# USBHeaders.net
KiCad netlist of a schematic drawn in Altium Designer
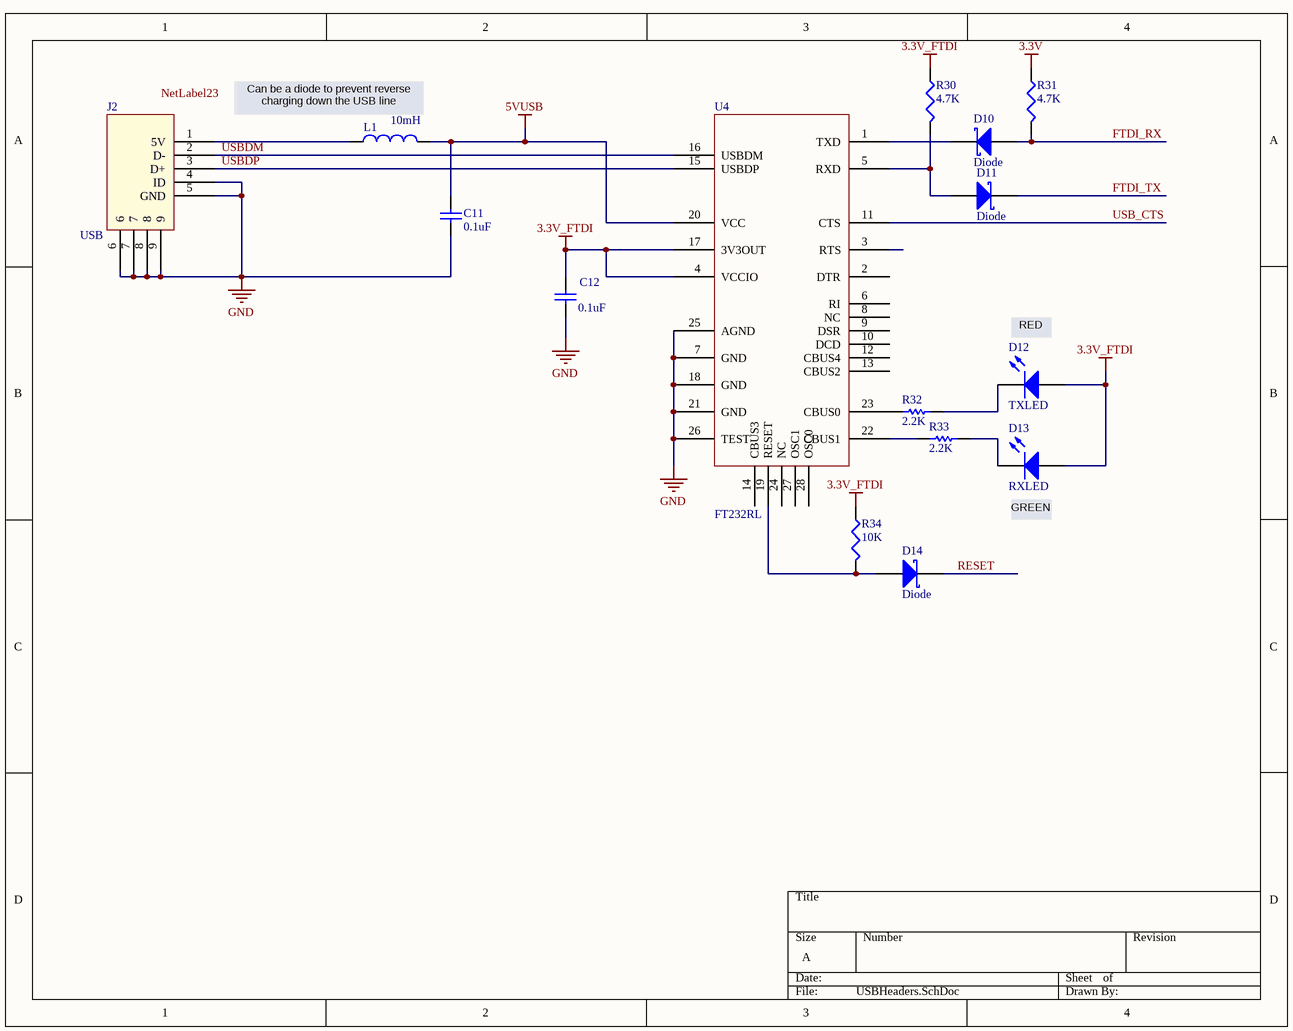
[diagram p0: USBHeaders.SchDoc]

(export (version "E")
  (design (tool "Eeschema 10.0.6"))
  (components
    (comp (ref "C11")
      (value "0.1uF")
      (footprint "0402")
      (description "Capacitor")
      (fields (field (name "PUBLISHER") "Altium Limited"))
      (libsource (lib "Miscellaneous Devices") (part "Cap"))
    )
    (comp (ref "C12")
      (value "0.1uF")
      (footprint "0402")
      (description "Capacitor")
      (fields (field (name "PUBLISHER") "Altium Limited"))
      (libsource (lib "Miscellaneous Devices") (part "Cap"))
    )
    (comp (ref "D10")
      (value "Diode")
      (footprint "SurfaceMount(603)")
      (libsource (lib "mrone") (part "SchottkeyDiode"))
    )
    (comp (ref "D11")
      (value "Diode")
      (footprint "SurfaceMount(603)")
      (libsource (lib "mrone") (part "SchottkeyDiode"))
    )
    (comp (ref "D12")
      (value "TXLED")
      (footprint "SurfaceMount(603)")
      (description "Typical RED, GREEN, YELLOW, AMBER GaAs LED")
      (fields (field (name "PUBLISHER") "Altium Limited"))
      (libsource (lib "Miscellaneous Devices") (part "LED2"))
    )
    (comp (ref "D13")
      (value "RXLED")
      (footprint "SurfaceMount(603)")
      (description "Typical RED, GREEN, YELLOW, AMBER GaAs LED")
      (fields (field (name "PUBLISHER") "Altium Limited"))
      (libsource (lib "Miscellaneous Devices") (part "LED2"))
    )
    (comp (ref "D14")
      (value "Diode")
      (footprint "SurfaceMount(603)")
      (libsource (lib "mrone") (part "SchottkeyDiode"))
    )
    (comp (ref "J2")
      (value "USB")
      (footprint "USB Minib (thru-hole)")
      (libsource (lib "mrone") (part "USB-ConnTH"))
    )
    (comp (ref "L1")
      (value "10mH")
      (footprint "2029")
      (description "Inductor")
      (fields (field (name "PUBLISHER") "Altium Limited"))
      (libsource (lib "Miscellaneous Devices") (part "Inductor"))
    )
    (comp (ref "R30")
      (value "4.7K")
      (footprint "J1-0603")
      (description "Resistor")
      (fields (field (name "Comment") "Res3") (field (name "PUBLISHER") "Altium Limited"))
      (libsource (lib "Miscellaneous Devices") (part "Res3"))
    )
    (comp (ref "R31")
      (value "4.7K")
      (footprint "J1-0603")
      (description "Resistor")
      (fields (field (name "Comment") "Res3") (field (name "PUBLISHER") "Altium Limited"))
      (libsource (lib "Miscellaneous Devices") (part "Res3"))
    )
    (comp (ref "R32")
      (value "2.2K")
      (footprint "J1-0603")
      (description "Resistor")
      (fields (field (name "PUBLISHER") "Altium Limited"))
      (libsource (lib "Miscellaneous Devices") (part "Res1"))
    )
    (comp (ref "R33")
      (value "2.2K")
      (footprint "J1-0603")
      (description "Resistor")
      (fields (field (name "PUBLISHER") "Altium Limited"))
      (libsource (lib "Miscellaneous Devices") (part "Res1"))
    )
    (comp (ref "R34")
      (value "10K")
      (footprint "J1-0603")
      (description "Resistor")
      (fields (field (name "Comment") "Res3") (field (name "PUBLISHER") "Altium Limited"))
      (libsource (lib "Miscellaneous Devices") (part "Res3"))
    )
    (comp (ref "U4") (value "FT232RL") (footprint "SSOP-28") (libsource (lib "mrone") (part "FT232RL")))
  )
  (nets
    (net (code "1") (name "/FTDI_RX") (class "Default")
      (node (ref "D10") (pin "2") (pinfunction "A_2") (pintype "passive"))
      (node (ref "R31") (pin "2") (pinfunction "2_2") (pintype "passive"))
    )
    (net (code "2") (name "/FTDI_TX") (class "Default")
      (node (ref "D11") (pin "1") (pinfunction "K_1") (pintype "passive"))
    )
    (net (code "4") (name "/RESET") (class "Default")
      (node (ref "D14") (pin "1") (pinfunction "K_1") (pintype "passive"))
    )
    (net (code "5") (name "/USBDM") (class "Default")
      (node (ref "J2") (pin "2") (pinfunction "D-_2") (pintype "passive"))
      (node (ref "U4") (pin "16") (pinfunction "USBDM_16") (pintype "passive"))
    )
    (net (code "6") (name "/USBDP") (class "Default")
      (node (ref "J2") (pin "3") (pinfunction "D+_3") (pintype "passive"))
      (node (ref "U4") (pin "15") (pinfunction "USBDP_15") (pintype "passive"))
    )
    (net (code "7") (name "/USB_CTS") (class "Default")
      (node (ref "U4") (pin "11") (pinfunction "CTS_11") (pintype "passive"))
    )
    (net (code "8") (name "3.3V") (class "Default")
      (node (ref "R31") (pin "1") (pinfunction "1_1") (pintype "passive"))
    )
    (net (code "9") (name "3.3V_FTDI") (class "Default")
      (node (ref "C12") (pin "2") (pinfunction "2_2") (pintype "passive"))
      (node (ref "D12") (pin "1") (pinfunction "A_1") (pintype "passive"))
      (node (ref "D13") (pin "1") (pinfunction "A_1") (pintype "passive"))
      (node (ref "R30") (pin "1") (pinfunction "1_1") (pintype "passive"))
      (node (ref "R34") (pin "1") (pinfunction "1_1") (pintype "passive"))
      (node (ref "U4") (pin "17") (pinfunction "3V3OUT_17") (pintype "passive"))
      (node (ref "U4") (pin "4") (pinfunction "VCCIO_4") (pintype "passive"))
    )
    (net (code "10") (name "5VUSB") (class "Default")
      (node (ref "C11") (pin "2") (pinfunction "2_2") (pintype "passive"))
      (node (ref "L1") (pin "2") (pinfunction "2_2") (pintype "passive"))
      (node (ref "U4") (pin "20") (pinfunction "VCC_20") (pintype "passive"))
    )
    (net (code "11") (name "GND") (class "Default")
      (node (ref "C11") (pin "1") (pinfunction "1_1") (pintype "passive"))
      (node (ref "C12") (pin "1") (pinfunction "1_1") (pintype "passive"))
      (node (ref "J2") (pin "4") (pinfunction "ID_4") (pintype "passive"))
      (node (ref "J2") (pin "5") (pinfunction "GND_5") (pintype "passive"))
      (node (ref "J2") (pin "6") (pinfunction "6_6") (pintype "passive"))
      (node (ref "J2") (pin "7") (pinfunction "7_7") (pintype "passive"))
      (node (ref "J2") (pin "8") (pinfunction "8_8") (pintype "passive"))
      (node (ref "J2") (pin "9") (pinfunction "9_9") (pintype "passive"))
      (node (ref "U4") (pin "18") (pinfunction "GND_18") (pintype "passive"))
      (node (ref "U4") (pin "21") (pinfunction "GND_21") (pintype "passive"))
      (node (ref "U4") (pin "25") (pinfunction "AGND_25") (pintype "passive"))
      (node (ref "U4") (pin "26") (pinfunction "TEST_26") (pintype "passive"))
      (node (ref "U4") (pin "7") (pinfunction "GND_7") (pintype "passive"))
    )
    (net (code "12") (name "Net-(D10-K)") (class "Default")
      (node (ref "D10") (pin "1") (pinfunction "K_1") (pintype "passive"))
      (node (ref "U4") (pin "1") (pinfunction "TXD_1") (pintype "passive"))
    )
    (net (code "13") (name "Net-(D11-A)") (class "Default")
      (node (ref "D11") (pin "2") (pinfunction "A_2") (pintype "passive"))
      (node (ref "R30") (pin "2") (pinfunction "2_2") (pintype "passive"))
      (node (ref "U4") (pin "5") (pinfunction "RXD_5") (pintype "passive"))
    )
    (net (code "14") (name "Net-(D12-K)") (class "Default")
      (node (ref "D12") (pin "2") (pinfunction "K_2") (pintype "passive"))
      (node (ref "R32") (pin "2") (pinfunction "2_2") (pintype "passive"))
    )
    (net (code "15") (name "Net-(D13-K)") (class "Default")
      (node (ref "D13") (pin "2") (pinfunction "K_2") (pintype "passive"))
      (node (ref "R33") (pin "2") (pinfunction "2_2") (pintype "passive"))
    )
    (net (code "16") (name "Net-(D14-A)") (class "Default")
      (node (ref "D14") (pin "2") (pinfunction "A_2") (pintype "passive"))
      (node (ref "R34") (pin "2") (pinfunction "2_2") (pintype "passive"))
      (node (ref "U4") (pin "19") (pinfunction "RESET_19") (pintype "passive"))
    )
    (net (code "17") (name "Net-(J2-5V)") (class "Default")
      (node (ref "J2") (pin "1") (pinfunction "5V_1") (pintype "passive"))
      (node (ref "L1") (pin "1") (pinfunction "1_1") (pintype "passive"))
    )
    (net (code "18") (name "Net-(U4-CBUS0)") (class "Default")
      (node (ref "R32") (pin "1") (pinfunction "1_1") (pintype "passive"))
      (node (ref "U4") (pin "23") (pinfunction "CBUS0_23") (pintype "passive"))
    )
    (net (code "19") (name "Net-(U4-CBUS1)") (class "Default")
      (node (ref "R33") (pin "1") (pinfunction "1_1") (pintype "passive"))
      (node (ref "U4") (pin "22") (pinfunction "CBUS1_22") (pintype "passive"))
    )
    (net (code "20") (name "unconnected-(U4-CBUS2-Pad13)") (class "Default")
      (node (ref "U4") (pin "13") (pinfunction "CBUS2_13") (pintype "passive"))
    )
    (net (code "21") (name "unconnected-(U4-CBUS3-Pad14)") (class "Default")
      (node (ref "U4") (pin "14") (pinfunction "CBUS3_14") (pintype "passive"))
    )
    (net (code "22") (name "unconnected-(U4-CBUS4-Pad12)") (class "Default")
      (node (ref "U4") (pin "12") (pinfunction "CBUS4_12") (pintype "passive"))
    )
    (net (code "23") (name "unconnected-(U4-DCD-Pad10)") (class "Default")
      (node (ref "U4") (pin "10") (pinfunction "DCD_10") (pintype "passive"))
    )
    (net (code "24") (name "unconnected-(U4-DSR-Pad9)") (class "Default")
      (node (ref "U4") (pin "9") (pinfunction "DSR_9") (pintype "passive"))
    )
    (net (code "25") (name "unconnected-(U4-DTR-Pad2)") (class "Default")
      (node (ref "U4") (pin "2") (pinfunction "DTR_2") (pintype "passive"))
    )
    (net (code "26") (name "unconnected-(U4-NC-Pad8)") (class "Default")
      (node (ref "U4") (pin "8") (pinfunction "NC_8") (pintype "passive"))
    )
    (net (code "27") (name "unconnected-(U4-NC-Pad24)") (class "Default")
      (node (ref "U4") (pin "24") (pinfunction "NC_24") (pintype "passive"))
    )
    (net (code "28") (name "unconnected-(U4-OSC0-Pad28)") (class "Default")
      (node (ref "U4") (pin "28") (pinfunction "OSC0_28") (pintype "passive"))
    )
    (net (code "29") (name "unconnected-(U4-OSC1-Pad27)") (class "Default")
      (node (ref "U4") (pin "27") (pinfunction "OSC1_27") (pintype "passive"))
    )
    (net (code "30") (name "unconnected-(U4-RI-Pad6)") (class "Default")
      (node (ref "U4") (pin "6") (pinfunction "RI_6") (pintype "passive"))
    )
    (net (code "31") (name "unconnected-(U4-RTS-Pad3)") (class "Default")
      (node (ref "U4") (pin "3") (pinfunction "RTS_3") (pintype "passive"))
    )
  )
)
